# STM32F042F4P6.net
KiCad netlist of a schematic drawn in Altium Designer
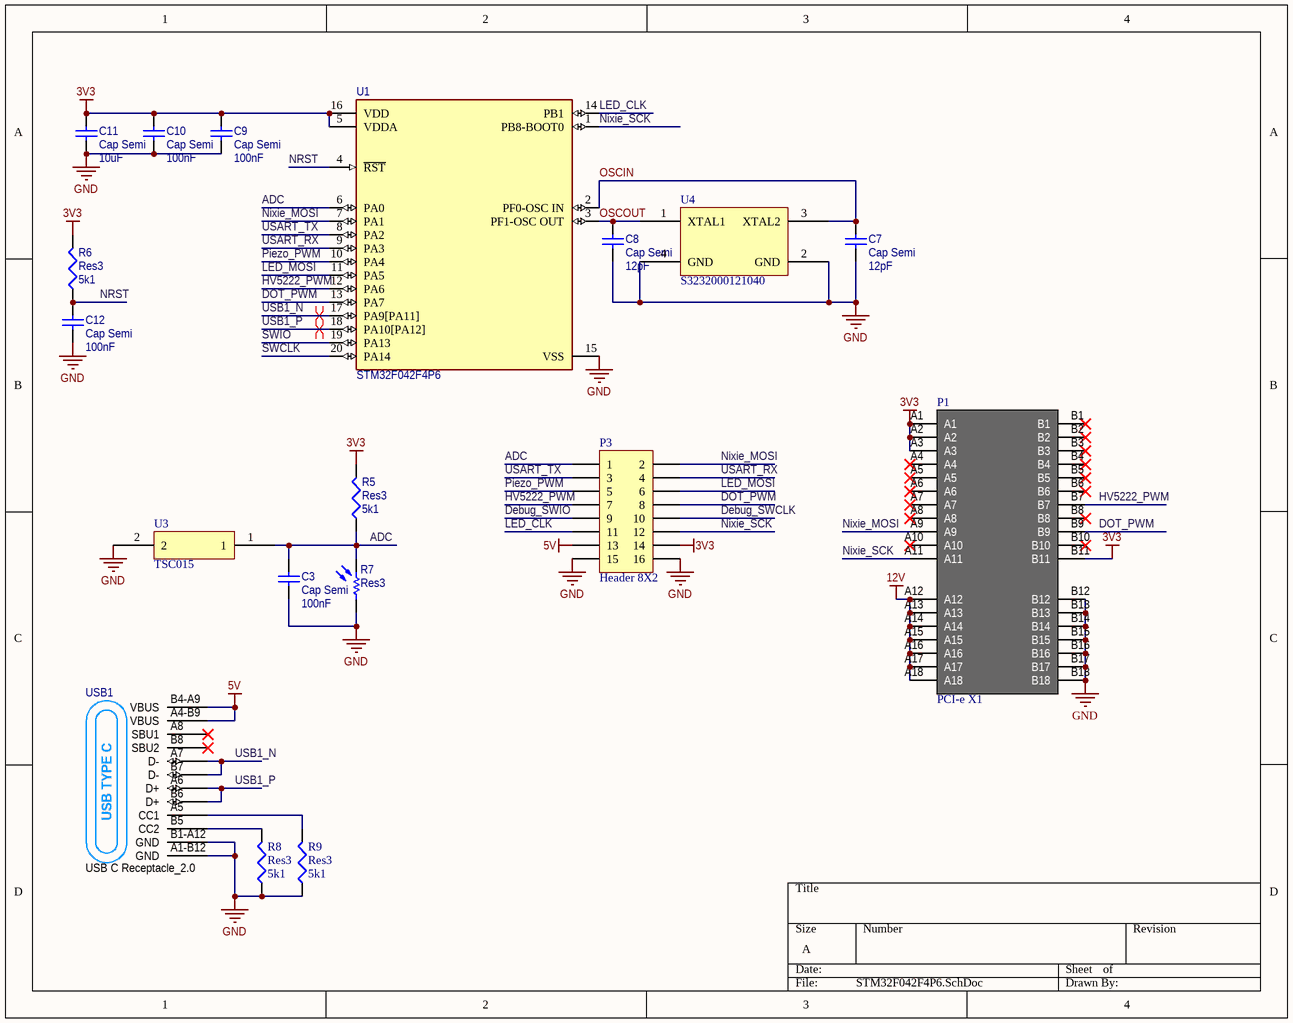
[diagram p0: STM32F042F4P6.SchDoc]

(export (version "E")
  (design (tool "Eeschema 10.0.6"))
  (components
    (comp (ref "C3")
      (value "Cap Semi")
      (footprint "0402")
      (description "Capacitor (Semiconductor SIM Model)")
      (fields (field (name "ALTIUM_VALUE") "100nF") (field (name "PUBLISHER") "Altium Limited"))
      (libsource (lib "Miscellaneous Devices") (part "Cap Semi"))
    )
    (comp (ref "C7")
      (value "Cap Semi")
      (footprint "0402")
      (description "Capacitor (Semiconductor SIM Model)")
      (fields (field (name "ALTIUM_VALUE") "12pF") (field (name "PUBLISHER") "Altium Limited"))
      (libsource (lib "Miscellaneous Devices") (part "Cap Semi"))
    )
    (comp (ref "C8")
      (value "Cap Semi")
      (footprint "0402")
      (description "Capacitor (Semiconductor SIM Model)")
      (fields (field (name "ALTIUM_VALUE") "12pF") (field (name "PUBLISHER") "Altium Limited"))
      (libsource (lib "Miscellaneous Devices") (part "Cap Semi"))
    )
    (comp (ref "C9")
      (value "Cap Semi")
      (footprint "0402")
      (description "Capacitor (Semiconductor SIM Model)")
      (fields (field (name "ALTIUM_VALUE") "100nF") (field (name "PUBLISHER") "Altium Limited"))
      (libsource (lib "Miscellaneous Devices") (part "Cap Semi"))
    )
    (comp (ref "C10")
      (value "Cap Semi")
      (footprint "0402")
      (description "Capacitor (Semiconductor SIM Model)")
      (fields (field (name "ALTIUM_VALUE") "100nF") (field (name "PUBLISHER") "Altium Limited"))
      (libsource (lib "Miscellaneous Devices") (part "Cap Semi"))
    )
    (comp (ref "C11")
      (value "Cap Semi")
      (footprint "1608[0603]")
      (description "Capacitor (Semiconductor SIM Model)")
      (fields (field (name "ALTIUM_VALUE") "10uF") (field (name "PUBLISHER") "Altium Limited"))
      (libsource (lib "Miscellaneous Devices") (part "Cap Semi"))
    )
    (comp (ref "C12")
      (value "Cap Semi")
      (footprint "0402")
      (description "Capacitor (Semiconductor SIM Model)")
      (fields (field (name "ALTIUM_VALUE") "100nF") (field (name "PUBLISHER") "Altium Limited"))
      (libsource (lib "Miscellaneous Devices") (part "Cap Semi"))
    )
    (comp (ref "P1")
      (value "PCI-e X1")
      (footprint "10018784-10210TLF")
      (libsource (lib "kwa") (part "PCI-e X1"))
    )
    (comp (ref "P3")
      (value "Header 8X2")
      (footprint "HDR2X8")
      (description "Header, 8-Pin, Dual row")
      (fields (field (name "PUBLISHER") "Altium Limited"))
      (libsource (lib "Miscellaneous Connectors") (part "Header 8X2"))
    )
    (comp (ref "R5")
      (value "Res3")
      (footprint "J1-0603")
      (description "Resistor")
      (fields (field (name "ALTIUM_VALUE") "5k1") (field (name "PUBLISHER") "Altium Limited"))
      (libsource (lib "Miscellaneous Devices") (part "Res3"))
    )
    (comp (ref "R6")
      (value "Res3")
      (footprint "J1-0603")
      (description "Resistor")
      (fields (field (name "ALTIUM_VALUE") "5k1") (field (name "PUBLISHER") "Altium Limited"))
      (libsource (lib "Miscellaneous Devices") (part "Res3"))
    )
    (comp (ref "R7")
      (value "Res3")
      (footprint "J1-0603")
      (description "Photoconductive Resistor, 200 kOhm, 100 V, 80 mW, -40 to 75 degC, 2-Pin THD, RoHS")
      (fields (field (name "MANUFACTURER") "Excelitas Technology"))
      (libsource (lib "Altium Content Vault") (part "PHOTO-RES-2"))
    )
    (comp (ref "R8")
      (value "Res3")
      (footprint "J1-0603")
      (description "Resistor")
      (fields (field (name "ALTIUM_VALUE") "5k1") (field (name "PUBLISHER") "Altium Limited"))
      (libsource (lib "Miscellaneous Devices") (part "Res3"))
    )
    (comp (ref "R9")
      (value "Res3")
      (footprint "J1-0603")
      (description "Resistor")
      (fields (field (name "ALTIUM_VALUE") "5k1") (field (name "PUBLISHER") "Altium Limited"))
      (libsource (lib "Miscellaneous Devices") (part "Res3"))
    )
    (comp (ref "U1")
      (value "STM32F042F4P6")
      (footprint "FP-TSSOP20-YA-MFG")
      (description "IC MCU 32BIT 16KB FLASH 20TSSOP")
      (fields
        (field (name "MANUFACTURER") "STMicroelectronics")
        (field (name "OCTOPART") "https://octopart.com/stm32f042f4p6-stmicroelectronics-34084829")
      )
      (libsource (lib "Altium Content Vault") (part "fb5839cf7c6cc5d149adc7a09845317"))
    )
    (comp (ref "U3")
      (value "TSC015")
      (footprint "TSC015")
      (description "Tactile Switch")
      (libsource (lib "Nixie_Clock") (part "TSC015"))
    )
    (comp (ref "U4")
      (value "S3232000121040")
      (footprint "SMD3225")
      (description "32MHz SMD Crystal Resonator")
      (libsource (lib "Nixie_Clock") (part "S3232000121040"))
    )
    (comp (ref "USB1")
      (value "USB C Receptacle_2.0")
      (footprint "TYPE-C16PIN-CONNECTOR")
      (libsource (lib "kwa") (part "USB C Receptacle_2.0"))
    )
  )
  (nets
    (net (code "1") (name "/ADC") (class "Default")
      (node (ref "C3") (pin "2") (pinfunction "2_2") (pintype "passive"))
      (node (ref "P3") (pin "1") (pinfunction "1_1") (pintype "passive"))
      (node (ref "R5") (pin "1") (pinfunction "1_1") (pintype "passive"))
      (node (ref "R7") (pin "2") (pinfunction "2_2") (pintype "passive"))
      (node (ref "U1") (pin "6") (pinfunction "PA0_6") (pintype "bidirectional"))
      (node (ref "U3") (pin "1") (pinfunction "1_1") (pintype "passive"))
    )
    (net (code "2") (name "/DOT_PWM") (class "Default")
      (node (ref "P1") (pin "B9") (pinfunction "B9_B9") (pintype "passive"))
      (node (ref "P3") (pin "8") (pinfunction "8_8") (pintype "passive"))
      (node (ref "U1") (pin "13") (pinfunction "PA7_13") (pintype "bidirectional"))
    )
    (net (code "3") (name "/Debug_SWCLK") (class "Default")
      (node (ref "P3") (pin "10") (pinfunction "10_10") (pintype "passive"))
    )
    (net (code "4") (name "/Debug_SWIO") (class "Default")
      (node (ref "P3") (pin "9") (pinfunction "9_9") (pintype "passive"))
    )
    (net (code "5") (name "/HV5222_PWM") (class "Default")
      (node (ref "P1") (pin "B7") (pinfunction "B7_B7") (pintype "passive"))
      (node (ref "P3") (pin "7") (pinfunction "7_7") (pintype "passive"))
      (node (ref "U1") (pin "12") (pinfunction "PA6_12") (pintype "bidirectional"))
    )
    (net (code "6") (name "/LED_CLK") (class "Default")
      (node (ref "P3") (pin "11") (pinfunction "11_11") (pintype "passive"))
      (node (ref "U1") (pin "14") (pinfunction "PB1_14") (pintype "bidirectional"))
    )
    (net (code "7") (name "/LED_MOSI") (class "Default")
      (node (ref "P3") (pin "6") (pinfunction "6_6") (pintype "passive"))
      (node (ref "U1") (pin "11") (pinfunction "PA5_11") (pintype "bidirectional"))
    )
    (net (code "8") (name "/NRST") (class "Default")
      (node (ref "C12") (pin "2") (pinfunction "2_2") (pintype "passive"))
      (node (ref "R6") (pin "1") (pinfunction "1_1") (pintype "passive"))
      (node (ref "U1") (pin "4") (pinfunction "~{RST}_4") (pintype "input"))
    )
    (net (code "9") (name "/Nixie_MOSI") (class "Default")
      (node (ref "P1") (pin "A9") (pinfunction "A9_A9") (pintype "passive"))
      (node (ref "P3") (pin "2") (pinfunction "2_2") (pintype "passive"))
      (node (ref "U1") (pin "7") (pinfunction "PA1_7") (pintype "bidirectional"))
    )
    (net (code "10") (name "/Nixie_SCK") (class "Default")
      (node (ref "P1") (pin "A11") (pinfunction "A11_A11") (pintype "passive"))
      (node (ref "P3") (pin "12") (pinfunction "12_12") (pintype "passive"))
      (node (ref "U1") (pin "1") (pinfunction "PB8-BOOT0_1") (pintype "bidirectional"))
    )
    (net (code "11") (name "/OSCIN") (class "Default")
      (node (ref "C7") (pin "2") (pinfunction "2_2") (pintype "passive"))
      (node (ref "U1") (pin "2") (pinfunction "PF0-OSC_IN_2") (pintype "bidirectional"))
      (node (ref "U4") (pin "3") (pinfunction "XTAL2_3") (pintype "passive"))
    )
    (net (code "12") (name "/OSCOUT") (class "Default")
      (node (ref "C8") (pin "1") (pinfunction "1_1") (pintype "passive"))
      (node (ref "U1") (pin "3") (pinfunction "PF1-OSC_OUT_3") (pintype "bidirectional"))
      (node (ref "U4") (pin "1") (pinfunction "XTAL1_1") (pintype "passive"))
    )
    (net (code "13") (name "/Piezo_PWM") (class "Default")
      (node (ref "P3") (pin "5") (pinfunction "5_5") (pintype "passive"))
      (node (ref "U1") (pin "10") (pinfunction "PA4_10") (pintype "bidirectional"))
    )
    (net (code "14") (name "/SWCLK") (class "Default")
      (node (ref "U1") (pin "20") (pinfunction "PA14_20") (pintype "bidirectional"))
    )
    (net (code "15") (name "/SWIO") (class "Default")
      (node (ref "U1") (pin "19") (pinfunction "PA13_19") (pintype "bidirectional"))
    )
    (net (code "16") (name "/USART_RX") (class "Default")
      (node (ref "P3") (pin "4") (pinfunction "4_4") (pintype "passive"))
      (node (ref "U1") (pin "9") (pinfunction "PA3_9") (pintype "bidirectional"))
    )
    (net (code "17") (name "/USART_TX") (class "Default")
      (node (ref "P3") (pin "3") (pinfunction "3_3") (pintype "passive"))
      (node (ref "U1") (pin "8") (pinfunction "PA2_8") (pintype "bidirectional"))
    )
    (net (code "18") (name "/USB1_N") (class "Default")
      (node (ref "U1") (pin "17") (pinfunction "PA9[PA11]_17") (pintype "bidirectional"))
      (node (ref "USB1") (pin "A7") (pinfunction "D-_A7") (pintype "bidirectional"))
      (node (ref "USB1") (pin "B7") (pinfunction "D-_B7") (pintype "bidirectional"))
    )
    (net (code "19") (name "/USB1_P") (class "Default")
      (node (ref "U1") (pin "18") (pinfunction "PA10[PA12]_18") (pintype "bidirectional"))
      (node (ref "USB1") (pin "A6") (pinfunction "D+_A6") (pintype "bidirectional"))
      (node (ref "USB1") (pin "B6") (pinfunction "D+_B6") (pintype "bidirectional"))
    )
    (net (code "20") (name "3V3") (class "Default")
      (node (ref "C10") (pin "2") (pinfunction "2_2") (pintype "passive"))
      (node (ref "C11") (pin "2") (pinfunction "2_2") (pintype "passive"))
      (node (ref "C9") (pin "2") (pinfunction "2_2") (pintype "passive"))
      (node (ref "P1") (pin "A1") (pinfunction "A1_A1") (pintype "passive"))
      (node (ref "P1") (pin "A2") (pinfunction "A2_A2") (pintype "passive"))
      (node (ref "P1") (pin "A3") (pinfunction "A3_A3") (pintype "passive"))
      (node (ref "P1") (pin "B11") (pinfunction "B11_B11") (pintype "passive"))
      (node (ref "P3") (pin "14") (pinfunction "14_14") (pintype "passive"))
      (node (ref "R5") (pin "2") (pinfunction "2_2") (pintype "passive"))
      (node (ref "R6") (pin "2") (pinfunction "2_2") (pintype "passive"))
      (node (ref "U1") (pin "16") (pinfunction "VDD_16") (pintype "power_in"))
      (node (ref "U1") (pin "5") (pinfunction "VDDA_5") (pintype "power_in"))
    )
    (net (code "21") (name "5V") (class "Default")
      (node (ref "P3") (pin "13") (pinfunction "13_13") (pintype "passive"))
      (node (ref "USB1") (pin "A4-B9") (pinfunction "VBUS_A4-B9") (pintype "power_in"))
      (node (ref "USB1") (pin "B4-A9") (pinfunction "VBUS_B4-A9") (pintype "power_in"))
    )
    (net (code "22") (name "12V") (class "Default")
      (node (ref "P1") (pin "A12") (pinfunction "A12_A12") (pintype "passive"))
      (node (ref "P1") (pin "A13") (pinfunction "A13_A13") (pintype "passive"))
      (node (ref "P1") (pin "A14") (pinfunction "A14_A14") (pintype "passive"))
      (node (ref "P1") (pin "A15") (pinfunction "A15_A15") (pintype "passive"))
      (node (ref "P1") (pin "A16") (pinfunction "A16_A16") (pintype "passive"))
      (node (ref "P1") (pin "A17") (pinfunction "A17_A17") (pintype "passive"))
      (node (ref "P1") (pin "A18") (pinfunction "A18_A18") (pintype "passive"))
    )
    (net (code "23") (name "GND") (class "Default")
      (node (ref "C10") (pin "1") (pinfunction "1_1") (pintype "passive"))
      (node (ref "C11") (pin "1") (pinfunction "1_1") (pintype "passive"))
      (node (ref "C12") (pin "1") (pinfunction "1_1") (pintype "passive"))
      (node (ref "C3") (pin "1") (pinfunction "1_1") (pintype "passive"))
      (node (ref "C7") (pin "1") (pinfunction "1_1") (pintype "passive"))
      (node (ref "C8") (pin "2") (pinfunction "2_2") (pintype "passive"))
      (node (ref "C9") (pin "1") (pinfunction "1_1") (pintype "passive"))
      (node (ref "P1") (pin "B12") (pinfunction "B12_B12") (pintype "passive"))
      (node (ref "P1") (pin "B13") (pinfunction "B13_B13") (pintype "passive"))
      (node (ref "P1") (pin "B14") (pinfunction "B14_B14") (pintype "passive"))
      (node (ref "P1") (pin "B15") (pinfunction "B15_B15") (pintype "passive"))
      (node (ref "P1") (pin "B16") (pinfunction "B16_B16") (pintype "passive"))
      (node (ref "P1") (pin "B17") (pinfunction "B17_B17") (pintype "passive"))
      (node (ref "P1") (pin "B18") (pinfunction "B18_B18") (pintype "passive"))
      (node (ref "P3") (pin "15") (pinfunction "15_15") (pintype "passive"))
      (node (ref "P3") (pin "16") (pinfunction "16_16") (pintype "passive"))
      (node (ref "R7") (pin "1") (pinfunction "1_1") (pintype "passive"))
      (node (ref "R8") (pin "1") (pinfunction "1_1") (pintype "passive"))
      (node (ref "R9") (pin "1") (pinfunction "1_1") (pintype "passive"))
      (node (ref "U1") (pin "15") (pinfunction "VSS_15") (pintype "power_in"))
      (node (ref "U3") (pin "2") (pinfunction "2_2") (pintype "power_in"))
      (node (ref "U4") (pin "2") (pinfunction "GND_2") (pintype "power_in"))
      (node (ref "U4") (pin "4") (pinfunction "GND_4") (pintype "power_in"))
      (node (ref "USB1") (pin "A1-B12") (pinfunction "GND_A1-B12") (pintype "power_in"))
      (node (ref "USB1") (pin "B1-A12") (pinfunction "GND_B1-A12") (pintype "power_in"))
    )
    (net (code "24") (name "Net-(USB1-CC1)") (class "Default")
      (node (ref "R9") (pin "2") (pinfunction "2_2") (pintype "passive"))
      (node (ref "USB1") (pin "A5") (pinfunction "CC1_A5") (pintype "passive"))
    )
    (net (code "25") (name "Net-(USB1-CC2)") (class "Default")
      (node (ref "R8") (pin "2") (pinfunction "2_2") (pintype "passive"))
      (node (ref "USB1") (pin "B5") (pinfunction "CC2_B5") (pintype "passive"))
    )
    (net (code "26") (name "unconnected-(P1-PadA4)") (class "Default")
      (node (ref "P1") (pin "A4") (pinfunction "A4_A4") (pintype "passive+no_connect"))
    )
    (net (code "27") (name "unconnected-(P1-PadA5)") (class "Default")
      (node (ref "P1") (pin "A5") (pinfunction "A5_A5") (pintype "passive+no_connect"))
    )
    (net (code "28") (name "unconnected-(P1-PadA6)") (class "Default")
      (node (ref "P1") (pin "A6") (pinfunction "A6_A6") (pintype "passive+no_connect"))
    )
    (net (code "29") (name "unconnected-(P1-PadA7)") (class "Default")
      (node (ref "P1") (pin "A7") (pinfunction "A7_A7") (pintype "passive+no_connect"))
    )
    (net (code "30") (name "unconnected-(P1-PadA8)") (class "Default")
      (node (ref "P1") (pin "A8") (pinfunction "A8_A8") (pintype "passive+no_connect"))
    )
    (net (code "31") (name "unconnected-(P1-PadA10)") (class "Default")
      (node (ref "P1") (pin "A10") (pinfunction "A10_A10") (pintype "passive+no_connect"))
    )
    (net (code "32") (name "unconnected-(P1-PadB1)") (class "Default")
      (node (ref "P1") (pin "B1") (pinfunction "B1_B1") (pintype "passive+no_connect"))
    )
    (net (code "33") (name "unconnected-(P1-PadB2)") (class "Default")
      (node (ref "P1") (pin "B2") (pinfunction "B2_B2") (pintype "passive+no_connect"))
    )
    (net (code "34") (name "unconnected-(P1-PadB3)") (class "Default")
      (node (ref "P1") (pin "B3") (pinfunction "B3_B3") (pintype "passive+no_connect"))
    )
    (net (code "35") (name "unconnected-(P1-PadB4)") (class "Default")
      (node (ref "P1") (pin "B4") (pinfunction "B4_B4") (pintype "passive+no_connect"))
    )
    (net (code "36") (name "unconnected-(P1-PadB5)") (class "Default")
      (node (ref "P1") (pin "B5") (pinfunction "B5_B5") (pintype "passive+no_connect"))
    )
    (net (code "37") (name "unconnected-(P1-PadB6)") (class "Default")
      (node (ref "P1") (pin "B6") (pinfunction "B6_B6") (pintype "passive+no_connect"))
    )
    (net (code "38") (name "unconnected-(P1-PadB8)") (class "Default")
      (node (ref "P1") (pin "B8") (pinfunction "B8_B8") (pintype "passive+no_connect"))
    )
    (net (code "39") (name "unconnected-(P1-PadB10)") (class "Default")
      (node (ref "P1") (pin "B10") (pinfunction "B10_B10") (pintype "passive+no_connect"))
    )
    (net (code "40") (name "unconnected-(USB1-SBU1-PadA8)") (class "Default")
      (node (ref "USB1") (pin "A8") (pinfunction "SBU1_A8") (pintype "passive+no_connect"))
    )
    (net (code "41") (name "unconnected-(USB1-SBU2-PadB8)") (class "Default")
      (node (ref "USB1") (pin "B8") (pinfunction "SBU2_B8") (pintype "passive+no_connect"))
    )
  )
)
